# 02-PowerIn.net
KiCad netlist of a schematic drawn in Altium Designer
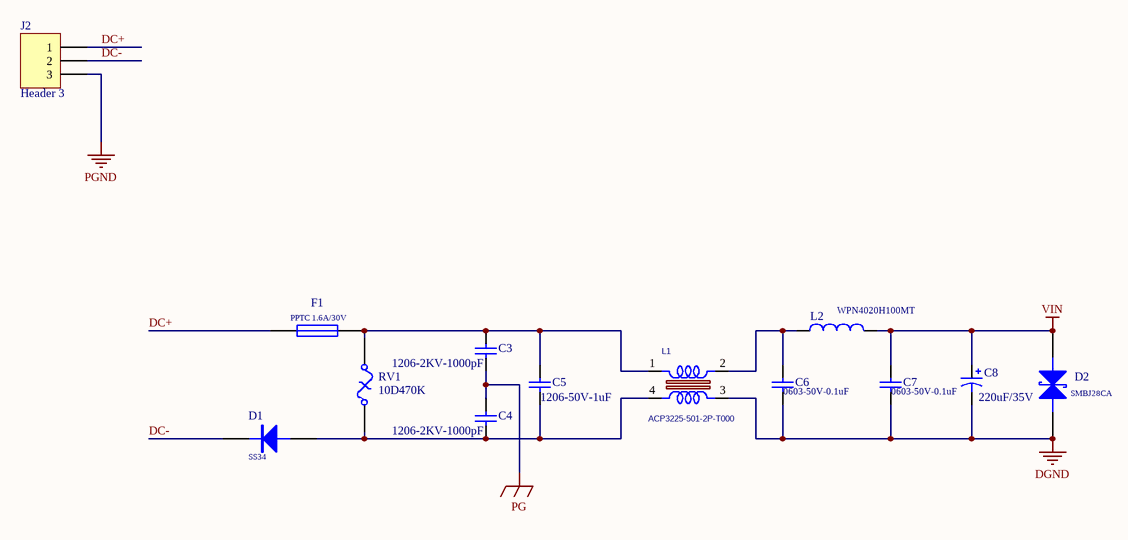
[diagram p0: 02-PowerIn.SchDoc]

(export (version "E")
  (design (tool "Eeschema 10.0.6"))
  (components
    (comp (ref "C3")
      (value "1206-2KV-1000pF")
      (footprint "1206C")
      (description "Capacitor")
      (fields (field (name "PUBLISHER") "Altium Limited"))
      (libsource (lib "Miscellaneous Devices") (part "Cap"))
    )
    (comp (ref "C4")
      (value "1206-2KV-1000pF")
      (footprint "1206C")
      (description "Capacitor")
      (fields (field (name "PUBLISHER") "Altium Limited"))
      (libsource (lib "Miscellaneous Devices") (part "Cap"))
    )
    (comp (ref "C5")
      (value "1206-50V-1uF")
      (footprint "1206C")
      (description "Capacitor")
      (fields (field (name "PUBLISHER") "Altium Limited"))
      (libsource (lib "Miscellaneous Devices") (part "Cap"))
    )
    (comp (ref "C6")
      (value "0603-50V-0.1uF")
      (footprint "0603C")
      (description "Capacitor")
      (fields (field (name "PUBLISHER") "Altium Limited"))
      (libsource (lib "Miscellaneous Devices") (part "Cap"))
    )
    (comp (ref "C7")
      (value "0603-50V-0.1uF")
      (footprint "0603C")
      (description "Capacitor")
      (fields (field (name "PUBLISHER") "Altium Limited"))
      (libsource (lib "Miscellaneous Devices") (part "Cap"))
    )
    (comp (ref "C8")
      (value "220uF/35V")
      (footprint "CAP-D8.0XH10.5")
      (description "Polarized Capacitor (Radial)")
      (fields (field (name "Comment") "CK1V221MCRF10") (field (name "PUBLISHER") "Altium Limited"))
      (libsource (lib "Miscellaneous Devices") (part "Cap Pol1"))
    )
    (comp (ref "D1")
      (value "SS34")
      (footprint "SMA")
      (description "Diode")
      (libsource (lib "*") (part "DIODE"))
    )
    (comp (ref "D2") (value "SMBJ28CA") (footprint "SMB-TVS") (libsource (lib "*") (part "TVSC")))
    (comp (ref "F1")
      (value "PPTC 1.6A/30V")
      (footprint "F-1.60A-30V")
      (description "Fuse")
      (fields (field (name "PUBLISHER") "Altium Limited"))
      (libsource (lib "Miscellaneous Devices") (part "Fuse 1"))
    )
    (comp (ref "J2")
      (value "Header 3")
      (footprint "KF2EDGR-5.08-3P")
      (description "Header, 3-Pin")
      (fields (field (name "PUBLISHER") "Altium Limited"))
      (libsource (lib "Miscellaneous Connectors") (part "Header 3"))
    )
    (comp (ref "L1")
      (value "ACP3225-501-2P-T000")
      (footprint "1210_4P")
      (description "Inductor, TDK,500ohm@100MHz,±25%,2A ,0.4ohm")
      (fields (field (name "MANUFACTURER") "Sunlord"))
      (libsource (lib "*") (part "Common Choke"))
    )
    (comp (ref "L2")
      (value "WPN4020H100MT")
      (footprint "4012")
      (description "贴片功率电感")
      (fields (field (name "PUBLISHER") "Altium Limited"))
      (libsource (lib "Miscellaneous Devices") (part "Inductor"))
    )
    (comp (ref "RV1")
      (value "10D470K")
      (footprint "PS-RES-12.5*5.4")
      (description "Thermal Fuse")
      (fields (field (name "PUBLISHER") "Altium Limited"))
      (libsource (lib "Miscellaneous Devices") (part "Fuse Thermal"))
    )
  )
  (nets
    (net (code "1") (name "/DC+") (class "Default")
      (node (ref "F1") (pin "2") (pinfunction "2_2") (pintype "passive"))
      (node (ref "J2") (pin "1") (pinfunction "1_1") (pintype "passive"))
    )
    (net (code "2") (name "/DC-") (class "Default")
      (node (ref "D1") (pin "2") (pinfunction "2_2") (pintype "passive"))
      (node (ref "J2") (pin "2") (pinfunction "2_2") (pintype "passive"))
    )
    (net (code "3") (name "DGND") (class "Default")
      (node (ref "C6") (pin "2") (pinfunction "2_2") (pintype "passive"))
      (node (ref "C7") (pin "2") (pinfunction "2_2") (pintype "passive"))
      (node (ref "C8") (pin "2") (pinfunction "2_2") (pintype "passive"))
      (node (ref "D2") (pin "1") (pinfunction "A_1") (pintype "passive"))
      (node (ref "L1") (pin "3") (pinfunction "3_3") (pintype "passive"))
    )
    (net (code "4") (name "Net-(C3-Pad2)") (class "Default")
      (node (ref "C3") (pin "2") (pinfunction "2_2") (pintype "passive"))
      (node (ref "C5") (pin "2") (pinfunction "2_2") (pintype "passive"))
      (node (ref "F1") (pin "1") (pinfunction "1_1") (pintype "passive"))
      (node (ref "L1") (pin "1") (pinfunction "1_1") (pintype "passive"))
      (node (ref "RV1") (pin "2") (pinfunction "2_2") (pintype "passive"))
    )
    (net (code "5") (name "Net-(C4-Pad1)") (class "Default")
      (node (ref "C4") (pin "1") (pinfunction "1_1") (pintype "passive"))
      (node (ref "C5") (pin "1") (pinfunction "1_1") (pintype "passive"))
      (node (ref "D1") (pin "1") (pinfunction "1_1") (pintype "passive"))
      (node (ref "L1") (pin "4") (pinfunction "4_4") (pintype "passive"))
      (node (ref "RV1") (pin "1") (pinfunction "1_1") (pintype "passive"))
    )
    (net (code "6") (name "Net-(C6-Pad1)") (class "Default")
      (node (ref "C6") (pin "1") (pinfunction "1_1") (pintype "passive"))
      (node (ref "L1") (pin "2") (pinfunction "2_2") (pintype "passive"))
      (node (ref "L2") (pin "1") (pinfunction "1_1") (pintype "passive"))
    )
    (net (code "7") (name "PG") (class "Default")
      (node (ref "C3") (pin "1") (pinfunction "1_1") (pintype "passive"))
      (node (ref "C4") (pin "2") (pinfunction "2_2") (pintype "passive"))
    )
    (net (code "8") (name "PGND") (class "Default")
      (node (ref "J2") (pin "3") (pinfunction "3_3") (pintype "passive"))
    )
    (net (code "9") (name "VIN") (class "Default")
      (node (ref "C7") (pin "1") (pinfunction "1_1") (pintype "passive"))
      (node (ref "C8") (pin "1") (pinfunction "1_1") (pintype "passive"))
      (node (ref "D2") (pin "2") (pinfunction "K_2") (pintype "passive"))
      (node (ref "L2") (pin "2") (pinfunction "2_2") (pintype "passive"))
    )
  )
)
